# lightbarrier_breakout.net
KiCad netlist of a schematic drawn in EAGLE
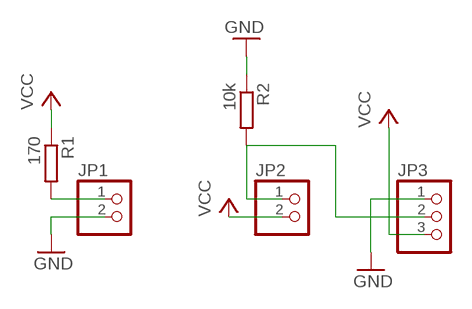
[diagram p0: schematic, sheet 1]

(export (version "E")
  (design (tool "Eeschema 10.0.6"))
  (components
    (comp (ref "JP1")
      (value "PINHD-1X2")
      (footprint "eagle-import:1X02")
      (libsource (lib "eagle-import") (part "PINHD-1X2"))
    )
    (comp (ref "JP2")
      (value "PINHD-1X2")
      (footprint "eagle-import:1X02")
      (libsource (lib "eagle-import") (part "PINHD-1X2"))
    )
    (comp (ref "JP3")
      (value "PINHD-1X3/90")
      (footprint "eagle-import:1X03_90")
      (libsource (lib "eagle-import") (part "PINHD-1X3/90"))
    )
    (comp (ref "R1")
      (value "170")
      (footprint "eagle-import:R0805")
      (libsource (lib "eagle-import") (part "R-EU_R0805"))
    )
    (comp (ref "R2")
      (value "10k")
      (footprint "eagle-import:R0805")
      (libsource (lib "eagle-import") (part "R-EU_R0805"))
    )
  )
  (nets
    (net (code "1") (name "GND") (class "Default")
      (node (ref "JP1") (pin "2") (pinfunction "2_2") (pintype "passive"))
      (node (ref "JP3") (pin "1") (pinfunction "1_1") (pintype "passive"))
      (node (ref "R2") (pin "1") (pinfunction "1_1") (pintype "passive"))
    )
    (net (code "2") (name "Net-(JP1-Pad1)") (class "Default")
      (node (ref "JP1") (pin "1") (pinfunction "1_1") (pintype "passive"))
      (node (ref "R1") (pin "2") (pinfunction "2_2") (pintype "passive"))
    )
    (net (code "3") (name "Net-(JP2-Pad1)") (class "Default")
      (node (ref "JP2") (pin "1") (pinfunction "1_1") (pintype "passive"))
      (node (ref "JP3") (pin "2") (pinfunction "2_2") (pintype "passive"))
      (node (ref "R2") (pin "2") (pinfunction "2_2") (pintype "passive"))
    )
    (net (code "4") (name "VCC") (class "Default")
      (node (ref "JP2") (pin "2") (pinfunction "2_2") (pintype "passive"))
      (node (ref "JP3") (pin "3") (pinfunction "3_3") (pintype "passive"))
      (node (ref "R1") (pin "1") (pinfunction "1_1") (pintype "passive"))
    )
  )
)
